# Phare_Alim.net
KiCad netlist of a schematic drawn in Altium Designer
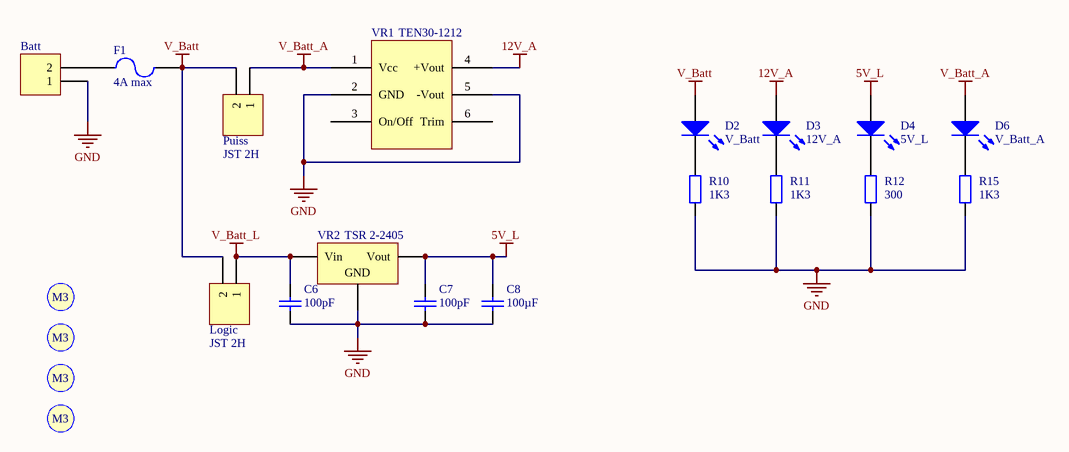
[diagram p0: Phare_Alim.SchDoc]

(export (version "E")
  (design (tool "Eeschema 10.0.6"))
  (components
    (comp (ref "Batt")
      (value "~")
      (footprint "Battery SALE")
      (description "Header, 2-Pin")
      (fields (field (name "PUBLISHER") "Altium Limited"))
      (libsource (lib "Miscellaneous Connectors") (part "Header 2"))
    )
    (comp (ref "C6")
      (value "100pF")
      (footprint "Capacitor 1206")
      (description "Capacitor")
      (fields (field (name "Comment") "Cap") (field (name "PUBLISHER") "Altium Limited"))
      (libsource (lib "Miscellaneous Devices") (part "Cap"))
    )
    (comp (ref "C7")
      (value "100pF")
      (footprint "Capacitor 1206")
      (description "Capacitor")
      (fields (field (name "Comment") "Cap") (field (name "PUBLISHER") "Altium Limited"))
      (libsource (lib "Miscellaneous Devices") (part "Cap"))
    )
    (comp (ref "C8")
      (value "100µF")
      (footprint "Condensateur")
      (description "Capacitor")
      (fields (field (name "Comment") "Cap") (field (name "PUBLISHER") "Altium Limited"))
      (libsource (lib "Miscellaneous Devices") (part "Cap"))
    )
    (comp (ref "D2")
      (value "V_Batt")
      (footprint "KP-3216SEC")
      (description "Typical RED, GREEN, YELLOW, AMBER GaAs LED")
      (fields (field (name "PUBLISHER") "Altium Limited"))
      (libsource (lib "Miscellaneous Devices") (part "LED2"))
    )
    (comp (ref "D3")
      (value "12V_A")
      (footprint "KP-3216SEC")
      (description "Typical RED, GREEN, YELLOW, AMBER GaAs LED")
      (fields (field (name "PUBLISHER") "Altium Limited"))
      (libsource (lib "Miscellaneous Devices") (part "LED2"))
    )
    (comp (ref "D4")
      (value "5V_L")
      (footprint "KP-3216SEC")
      (description "Typical RED, GREEN, YELLOW, AMBER GaAs LED")
      (fields (field (name "PUBLISHER") "Altium Limited"))
      (libsource (lib "Miscellaneous Devices") (part "LED2"))
    )
    (comp (ref "D6")
      (value "V_Batt_A")
      (footprint "KP-3216SEC")
      (description "Typical RED, GREEN, YELLOW, AMBER GaAs LED")
      (fields (field (name "PUBLISHER") "Altium Limited"))
      (libsource (lib "Miscellaneous Devices") (part "LED2"))
    )
    (comp (ref "F1")
      (value "4A max")
      (footprint "Fuse")
      (description "Fuse")
      (fields (field (name "PUBLISHER") "Altium Limited"))
      (libsource (lib "Miscellaneous Devices") (part "Fuse 2"))
    )
    (comp (ref "Logic")
      (value "JST 2H")
      (footprint "S2B-XH-A")
      (description "Header, 2-Pin")
      (fields (field (name "PUBLISHER") "Altium Limited"))
      (libsource (lib "") (part "Header 2_1"))
    )
    (comp (ref "Puiss")
      (value "JST 2H")
      (footprint "Molex_MiniFitJr_2x1H")
      (description "Header, 2-Pin")
      (fields (field (name "PUBLISHER") "Altium Limited"))
      (libsource (lib "") (part "Header 2_1"))
    )
    (comp (ref "R10")
      (value "1K3")
      (footprint "Resistor 1206")
      (description "Resistor")
      (fields (field (name "Comment") "Res2") (field (name "PUBLISHER") "Altium Limited"))
      (libsource (lib "Miscellaneous Devices") (part "Res2"))
    )
    (comp (ref "R11")
      (value "1K3")
      (footprint "Resistor 1206")
      (description "Resistor")
      (fields (field (name "Comment") "Res2") (field (name "PUBLISHER") "Altium Limited"))
      (libsource (lib "Miscellaneous Devices") (part "Res2"))
    )
    (comp (ref "R12")
      (value "300")
      (footprint "Resistor 1206")
      (description "Resistor")
      (fields (field (name "Comment") "Res2") (field (name "PUBLISHER") "Altium Limited"))
      (libsource (lib "Miscellaneous Devices") (part "Res2"))
    )
    (comp (ref "R15")
      (value "1K3")
      (footprint "Resistor 1206")
      (description "Resistor")
      (fields (field (name "Comment") "Res2") (field (name "PUBLISHER") "Altium Limited"))
      (libsource (lib "Miscellaneous Devices") (part "Res2"))
    )
    (comp (ref "S1")
      (value "Screw M3")
      (footprint "Screw M3")
      (libsource (lib "Robot_2020") (part "Screw M3"))
    )
    (comp (ref "S2")
      (value "Screw M3")
      (footprint "Screw M3")
      (libsource (lib "Robot_2020") (part "Screw M3"))
    )
    (comp (ref "S3")
      (value "Screw M3")
      (footprint "Screw M3")
      (libsource (lib "Robot_2020") (part "Screw M3"))
    )
    (comp (ref "S4")
      (value "Screw M3")
      (footprint "Screw M3")
      (libsource (lib "Robot_2020") (part "Screw M3"))
    )
    (comp (ref "VR1")
      (value "TEN30-1212")
      (footprint "TRACO_2x1inch")
      (description "TRACO TEN50")
      (fields (field (name "PUBLISHER") "Altium Limited"))
      (libsource (lib "Robot_2020") (part "TEN50"))
    )
    (comp (ref "VR2")
      (value "TSR 2-2405")
      (footprint "TRS")
      (description "Voltage Regulator")
      (fields (field (name "PUBLISHER") "Altium Limited"))
      (libsource (lib "Miscellaneous Devices") (part "Volt Reg"))
    )
  )
  (nets
    (net (code "1") (name "5V_L") (class "Default")
      (node (ref "C7") (pin "1") (pinfunction "1_1") (pintype "passive"))
      (node (ref "C8") (pin "1") (pinfunction "1_1") (pintype "passive"))
      (node (ref "D4") (pin "1") (pinfunction "A_1") (pintype "passive"))
      (node (ref "VR2") (pin "3") (pinfunction "Vout_3") (pintype "passive"))
    )
    (net (code "2") (name "12V_A") (class "Default")
      (node (ref "D3") (pin "1") (pinfunction "A_1") (pintype "passive"))
      (node (ref "VR1") (pin "4") (pinfunction "+Vout_4") (pintype "passive"))
    )
    (net (code "3") (name "GND") (class "Default")
      (node (ref "Batt") (pin "1") (pinfunction "1_1") (pintype "passive"))
      (node (ref "C6") (pin "2") (pinfunction "2_2") (pintype "passive"))
      (node (ref "C7") (pin "2") (pinfunction "2_2") (pintype "passive"))
      (node (ref "C8") (pin "2") (pinfunction "2_2") (pintype "passive"))
      (node (ref "R10") (pin "1") (pinfunction "1_1") (pintype "passive"))
      (node (ref "R11") (pin "1") (pinfunction "1_1") (pintype "passive"))
      (node (ref "R12") (pin "1") (pinfunction "1_1") (pintype "passive"))
      (node (ref "R15") (pin "1") (pinfunction "1_1") (pintype "passive"))
      (node (ref "VR1") (pin "2") (pinfunction "GND_2") (pintype "passive"))
      (node (ref "VR1") (pin "5") (pinfunction "-Vout_5") (pintype "passive"))
      (node (ref "VR2") (pin "2") (pinfunction "GND_2") (pintype "passive"))
    )
    (net (code "4") (name "Net-(Batt-Pad2)") (class "Default")
      (node (ref "Batt") (pin "2") (pinfunction "2_2") (pintype "passive"))
      (node (ref "F1") (pin "1") (pinfunction "1_1") (pintype "passive"))
    )
    (net (code "5") (name "Net-(D2-K)") (class "Default")
      (node (ref "D2") (pin "2") (pinfunction "K_2") (pintype "passive"))
      (node (ref "R10") (pin "2") (pinfunction "2_2") (pintype "passive"))
    )
    (net (code "6") (name "Net-(D3-K)") (class "Default")
      (node (ref "D3") (pin "2") (pinfunction "K_2") (pintype "passive"))
      (node (ref "R11") (pin "2") (pinfunction "2_2") (pintype "passive"))
    )
    (net (code "7") (name "Net-(D4-K)") (class "Default")
      (node (ref "D4") (pin "2") (pinfunction "K_2") (pintype "passive"))
      (node (ref "R12") (pin "2") (pinfunction "2_2") (pintype "passive"))
    )
    (net (code "8") (name "Net-(D6-K)") (class "Default")
      (node (ref "D6") (pin "2") (pinfunction "K_2") (pintype "passive"))
      (node (ref "R15") (pin "2") (pinfunction "2_2") (pintype "passive"))
    )
    (net (code "9") (name "V_Batt") (class "Default")
      (node (ref "D2") (pin "1") (pinfunction "A_1") (pintype "passive"))
      (node (ref "F1") (pin "2") (pinfunction "2_2") (pintype "passive"))
      (node (ref "Logic") (pin "2") (pinfunction "2_2") (pintype "passive"))
      (node (ref "Puiss") (pin "2") (pinfunction "2_2") (pintype "passive"))
    )
    (net (code "10") (name "V_Batt_A") (class "Default")
      (node (ref "D6") (pin "1") (pinfunction "A_1") (pintype "passive"))
      (node (ref "Puiss") (pin "1") (pinfunction "1_1") (pintype "passive"))
      (node (ref "VR1") (pin "1") (pinfunction "Vcc_1") (pintype "passive"))
    )
    (net (code "11") (name "V_Batt_L") (class "Default")
      (node (ref "C6") (pin "1") (pinfunction "1_1") (pintype "passive"))
      (node (ref "Logic") (pin "1") (pinfunction "1_1") (pintype "passive"))
      (node (ref "VR2") (pin "1") (pinfunction "Vin_1") (pintype "passive"))
    )
    (net (code "12") (name "unconnected-(VR1-On{slash}Off-Pad3)") (class "Default")
      (node (ref "VR1") (pin "3") (pinfunction "On/Off_3") (pintype "passive"))
    )
    (net (code "13") (name "unconnected-(VR1-Trim-Pad6)") (class "Default")
      (node (ref "VR1") (pin "6") (pinfunction "Trim_6") (pintype "passive"))
    )
  )
)
